# ENR_153_Board.net
KiCad netlist of a schematic drawn in EAGLE
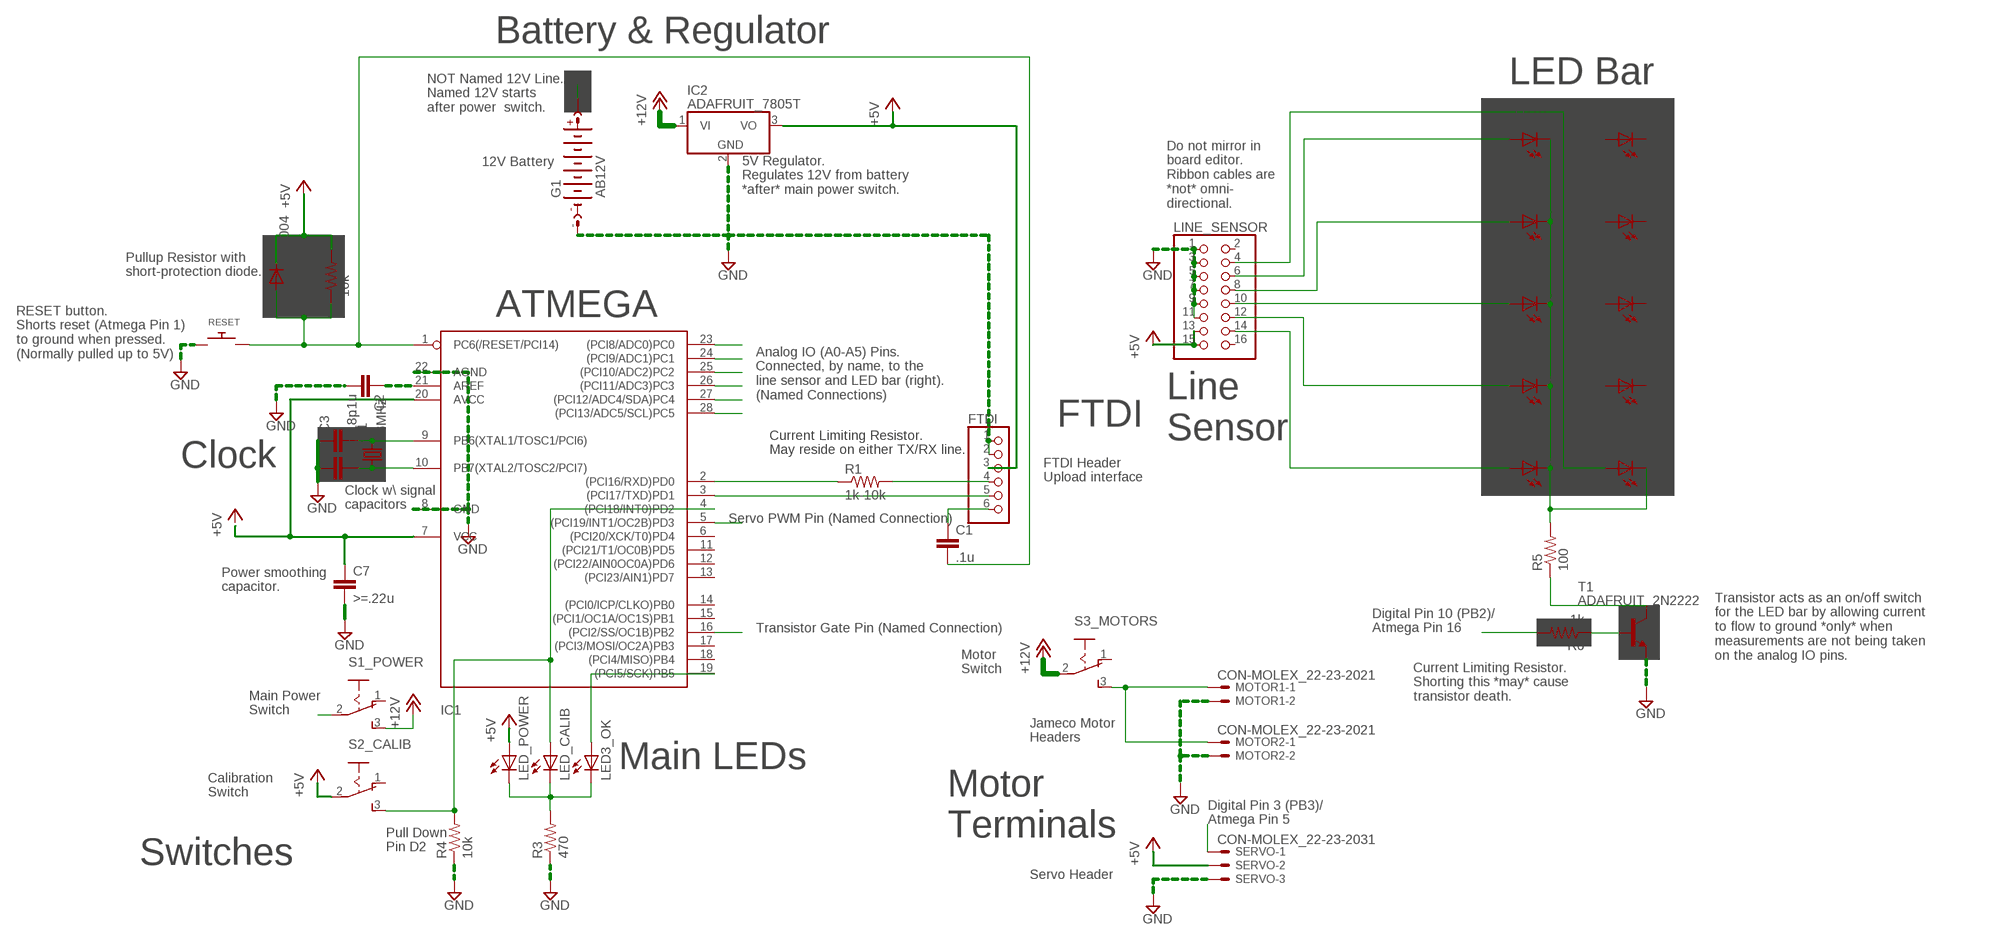
[diagram p0: schematic, sheet 1]

(export (version "E")
  (design (tool "Eeschema 10.0.6"))
  (components
    (comp (ref "C1")
      (value ".1u")
      (footprint "eagle-import:CAPACITOR-WIMA_C5B3")
      (libsource (lib "eagle-import") (part "CAPACITOR-WIMA_C5/3"))
    )
    (comp (ref "C2")
      (value ".1u")
      (footprint "eagle-import:CAPACITOR-WIMA_C5B3")
      (libsource (lib "eagle-import") (part "CAPACITOR-WIMA_C5/3"))
    )
    (comp (ref "C3")
      (value "18p")
      (footprint "eagle-import:CAPACITOR-WIMA_C5B3")
      (libsource (lib "eagle-import") (part "CAPACITOR-WIMA_C5/3"))
    )
    (comp (ref "C4")
      (value "18p")
      (footprint "eagle-import:CAPACITOR-WIMA_C5B3")
      (libsource (lib "eagle-import") (part "CAPACITOR-WIMA_C5/3"))
    )
    (comp (ref "C7")
      (value ">=.22u")
      (footprint "eagle-import:CAPACITOR-WIMA_C5B3")
      (libsource (lib "eagle-import") (part "CAPACITOR-WIMA_C5/3"))
    )
    (comp (ref "D1")
      (value "1N4004")
      (footprint "eagle-import:DIODE_DO35-7")
      (libsource (lib "eagle-import") (part "DIODE_1N4148DO35-7"))
    )
    (comp (ref "DZ1")
      (value "LB10")
      (footprint "eagle-import:LB10")
      (libsource (lib "eagle-import") (part "LB10"))
    )
    (comp (ref "FTDI")
      (value "PINHD-1X6")
      (footprint "eagle-import:1X06")
      (libsource (lib "eagle-import") (part "PINHD-1X6"))
    )
    (comp (ref "G1")
      (value "AB12V")
      (footprint "eagle-import:BATTERY_AB9V")
      (libsource (lib "eagle-import") (part "BATTERY_AB9V"))
    )
    (comp (ref "IC1")
      (value "ATMEGA168V-10P")
      (footprint "eagle-import:DIL28-3")
      (libsource (lib "eagle-import") (part "ATMEGA168PV-10"))
    )
    (comp (ref "IC2")
      (value "ADAFRUIT_7805T")
      (footprint "eagle-import:ADAFRUIT_TO220H")
      (libsource (lib "eagle-import") (part "ADAFRUIT_78T05"))
    )
    (comp (ref "LED3_OK")
      (value "ADAFRUIT_LEDSQR2X5")
      (footprint "eagle-import:ADAFRUIT_LED2X5")
      (libsource (lib "eagle-import") (part "ADAFRUIT_LEDSQR2X5"))
    )
    (comp (ref "LED_CALIB")
      (value "ADAFRUIT_LEDSQR2X5")
      (footprint "eagle-import:ADAFRUIT_LED2X5")
      (libsource (lib "eagle-import") (part "ADAFRUIT_LEDSQR2X5"))
    )
    (comp (ref "LED_POWER")
      (value "ADAFRUIT_LEDSQR2X5")
      (footprint "eagle-import:ADAFRUIT_LED2X5")
      (libsource (lib "eagle-import") (part "ADAFRUIT_LEDSQR2X5"))
    )
    (comp (ref "LINE_SENSOR")
      (value "PINHEAD_PINHD-2X8")
      (footprint "eagle-import:PINHEAD_2X08")
      (libsource (lib "eagle-import") (part "PINHEAD_PINHD-2X8"))
    )
    (comp (ref "MOTOR1")
      (value "CON-MOLEX_22-23-2021")
      (footprint "eagle-import:CON-MOLEX_22-23-2021")
      (fields (field (name "MF") "MOLEX") (field (name "MPN") "22-23-2021"))
      (libsource (lib "eagle-import") (part "CON-MOLEX_22-23-2021"))
    )
    (comp (ref "MOTOR2")
      (value "CON-MOLEX_22-23-2021")
      (footprint "eagle-import:CON-MOLEX_22-23-2021")
      (fields (field (name "MF") "MOLEX") (field (name "MPN") "22-23-2021"))
      (libsource (lib "eagle-import") (part "CON-MOLEX_22-23-2021"))
    )
    (comp (ref "Q1")
      (value "16MHz")
      (footprint "eagle-import:ADAFRUIT_HC49_S")
      (libsource (lib "eagle-import") (part "ADAFRUIT_CRYSTALHC49S"))
    )
    (comp (ref "R1")
      (value "1k-10k")
      (footprint "eagle-import:ADAFRUIT_0207_7")
      (libsource (lib "eagle-import") (part "ADAFRUIT_R-US_0207/7"))
    )
    (comp (ref "R2")
      (value "10k")
      (footprint "eagle-import:ADAFRUIT_0207_7")
      (libsource (lib "eagle-import") (part "ADAFRUIT_R-US_0207/7"))
    )
    (comp (ref "R3")
      (value "470")
      (footprint "eagle-import:ADAFRUIT_0207_7")
      (libsource (lib "eagle-import") (part "ADAFRUIT_R-US_0207/7"))
    )
    (comp (ref "R4")
      (value "10k")
      (footprint "eagle-import:ADAFRUIT_0207_7")
      (libsource (lib "eagle-import") (part "ADAFRUIT_R-US_0207/7"))
    )
    (comp (ref "R5")
      (value "100")
      (footprint "eagle-import:ADAFRUIT_0207_7")
      (libsource (lib "eagle-import") (part "ADAFRUIT_R-US_0207/7"))
    )
    (comp (ref "R6")
      (value "1k")
      (footprint "eagle-import:ADAFRUIT_0207_7")
      (libsource (lib "eagle-import") (part "ADAFRUIT_R-US_0207/7"))
    )
    (comp (ref "RESET")
      (value "ADAFRUIT_SWITCH_PUSHBUTTONEVQ-PE")
      (footprint "eagle-import:ADAFRUIT_TACT_PANA-EVQ")
      (libsource (lib "eagle-import") (part "ADAFRUIT_SWITCH_PUSHBUTTONEVQ-PE"))
    )
    (comp (ref "S1_POWER")
      (value "SWITCH_255SB")
      (footprint "eagle-import:SWITCH_255SB")
      (libsource (lib "eagle-import") (part "SWITCH_255SB"))
    )
    (comp (ref "S2_CALIB")
      (value "SWITCH_255SB")
      (footprint "eagle-import:SWITCH_255SB")
      (libsource (lib "eagle-import") (part "SWITCH_255SB"))
    )
    (comp (ref "S3_MOTORS")
      (value "SWITCH_255SB")
      (footprint "eagle-import:SWITCH_255SB")
      (libsource (lib "eagle-import") (part "SWITCH_255SB"))
    )
    (comp (ref "SERVO")
      (value "CON-MOLEX_22-23-2031")
      (footprint "eagle-import:CON-MOLEX_22-23-2031")
      (fields (field (name "MF") "MOLEX") (field (name "MPN") "22-23-2031"))
      (libsource (lib "eagle-import") (part "CON-MOLEX_22-23-2031"))
    )
    (comp (ref "T1")
      (value "ADAFRUIT_2N2222")
      (footprint "eagle-import:ADAFRUIT_TO92-EBC-OVAL")
      (libsource (lib "eagle-import") (part "ADAFRUIT_2N2222"))
    )
  )
  (nets
    (net (code "1") (name "+5V") (class "Default")
      (node (ref "C7") (pin "1") (pinfunction "1_1") (pintype "passive"))
      (node (ref "D1") (pin "C") (pinfunction "C_C") (pintype "passive"))
      (node (ref "FTDI") (pin "3") (pinfunction "3_3") (pintype "passive"))
      (node (ref "IC1") (pin "20") (pinfunction "AVCC_20") (pintype "bidirectional"))
      (node (ref "IC1") (pin "7") (pinfunction "VCC_7") (pintype "bidirectional"))
      (node (ref "IC2") (pin "3") (pinfunction "VO_3") (pintype "passive"))
      (node (ref "LED_POWER") (pin "A") (pinfunction "A_A") (pintype "passive"))
      (node (ref "LINE_SENSOR") (pin "13") (pinfunction "13_13") (pintype "passive"))
      (node (ref "LINE_SENSOR") (pin "15") (pinfunction "15_15") (pintype "passive"))
      (node (ref "R2") (pin "2") (pinfunction "2_2") (pintype "passive"))
      (node (ref "S2_CALIB") (pin "2") (pinfunction "P_2") (pintype "passive"))
      (node (ref "SERVO") (pin "2") (pinfunction "S_2") (pintype "passive"))
    )
    (net (code "2") (name "+12V") (class "Default")
      (node (ref "IC2") (pin "1") (pinfunction "VI_1") (pintype "input"))
      (node (ref "S1_POWER") (pin "3") (pinfunction "S_3") (pintype "passive"))
      (node (ref "S3_MOTORS") (pin "2") (pinfunction "P_2") (pintype "passive"))
    )
    (net (code "3") (name "/A0") (class "Default")
      (node (ref "DZ1") (pin "6") (pinfunction "A_6") (pintype "passive"))
      (node (ref "IC1") (pin "23") (pinfunction "(PCI8/ADC0)PC0_23") (pintype "bidirectional"))
      (node (ref "LINE_SENSOR") (pin "4") (pinfunction "4_4") (pintype "passive"))
    )
    (net (code "4") (name "/A1") (class "Default")
      (node (ref "DZ1") (pin "5") (pinfunction "A_5") (pintype "passive"))
      (node (ref "IC1") (pin "24") (pinfunction "(PCI9/ADC1)PC1_24") (pintype "bidirectional"))
      (node (ref "LINE_SENSOR") (pin "6") (pinfunction "6_6") (pintype "passive"))
    )
    (net (code "5") (name "/A2") (class "Default")
      (node (ref "DZ1") (pin "4") (pinfunction "A_4") (pintype "passive"))
      (node (ref "IC1") (pin "25") (pinfunction "(PCI10/ADC2)PC2_25") (pintype "bidirectional"))
      (node (ref "LINE_SENSOR") (pin "8") (pinfunction "8_8") (pintype "passive"))
    )
    (net (code "6") (name "/A3") (class "Default")
      (node (ref "DZ1") (pin "3") (pinfunction "A_3") (pintype "passive"))
      (node (ref "IC1") (pin "26") (pinfunction "(PCI11/ADC3)PC3_26") (pintype "bidirectional"))
      (node (ref "LINE_SENSOR") (pin "10") (pinfunction "10_10") (pintype "passive"))
    )
    (net (code "7") (name "/A4") (class "Default")
      (node (ref "DZ1") (pin "2") (pinfunction "A_2") (pintype "passive"))
      (node (ref "IC1") (pin "27") (pinfunction "(PCI12/ADC4/SDA)PC4_27") (pintype "bidirectional"))
      (node (ref "LINE_SENSOR") (pin "12") (pinfunction "12_12") (pintype "passive"))
    )
    (net (code "8") (name "/A5") (class "Default")
      (node (ref "DZ1") (pin "1") (pinfunction "A_1") (pintype "passive"))
      (node (ref "IC1") (pin "28") (pinfunction "(PCI13/ADC5/SCL)PC5_28") (pintype "bidirectional"))
      (node (ref "LINE_SENSOR") (pin "14") (pinfunction "14_14") (pintype "passive"))
    )
    (net (code "9") (name "/MAINS") (class "Default")
      (node (ref "G1") (pin "+") (pinfunction "+_+") (pintype "passive"))
      (node (ref "S1_POWER") (pin "2") (pinfunction "P_2") (pintype "passive"))
    )
    (net (code "10") (name "/SERVO") (class "Default")
      (node (ref "IC1") (pin "5") (pinfunction "(PCI19/INT1/OC2B)PD3_5") (pintype "bidirectional"))
      (node (ref "SERVO") (pin "1") (pinfunction "S_1") (pintype "passive"))
    )
    (net (code "11") (name "/TRANSISTOR_GATE") (class "Default")
      (node (ref "IC1") (pin "16") (pinfunction "(PCI2/SS/OC1B)PB2_16") (pintype "bidirectional"))
      (node (ref "R6") (pin "2") (pinfunction "2_2") (pintype "passive"))
    )
    (net (code "12") (name "GND") (class "Default")
      (node (ref "C2") (pin "2") (pinfunction "2_2") (pintype "passive"))
      (node (ref "C3") (pin "1") (pinfunction "1_1") (pintype "passive"))
      (node (ref "C4") (pin "1") (pinfunction "1_1") (pintype "passive"))
      (node (ref "C7") (pin "2") (pinfunction "2_2") (pintype "passive"))
      (node (ref "FTDI") (pin "1") (pinfunction "1_1") (pintype "passive"))
      (node (ref "FTDI") (pin "2") (pinfunction "2_2") (pintype "passive"))
      (node (ref "G1") (pin "-") (pinfunction "-_-") (pintype "passive"))
      (node (ref "IC1") (pin "22") (pinfunction "AGND_22") (pintype "bidirectional"))
      (node (ref "IC1") (pin "8") (pinfunction "GND_8") (pintype "bidirectional"))
      (node (ref "IC2") (pin "2") (pinfunction "GND_2") (pintype "passive"))
      (node (ref "LINE_SENSOR") (pin "1") (pinfunction "1_1") (pintype "passive"))
      (node (ref "LINE_SENSOR") (pin "11") (pinfunction "11_11") (pintype "passive"))
      (node (ref "LINE_SENSOR") (pin "3") (pinfunction "3_3") (pintype "passive"))
      (node (ref "LINE_SENSOR") (pin "5") (pinfunction "5_5") (pintype "passive"))
      (node (ref "LINE_SENSOR") (pin "7") (pinfunction "7_7") (pintype "passive"))
      (node (ref "LINE_SENSOR") (pin "9") (pinfunction "9_9") (pintype "passive"))
      (node (ref "MOTOR1") (pin "2") (pinfunction "S_2") (pintype "passive"))
      (node (ref "MOTOR2") (pin "2") (pinfunction "S_2") (pintype "passive"))
      (node (ref "R3") (pin "1") (pinfunction "1_1") (pintype "passive"))
      (node (ref "R4") (pin "1") (pinfunction "1_1") (pintype "passive"))
      (node (ref "RESET") (pin "P$1") (pinfunction "P$1_P$1") (pintype "passive"))
      (node (ref "SERVO") (pin "3") (pinfunction "S_3") (pintype "passive"))
      (node (ref "T1") (pin "E") (pinfunction "E_E") (pintype "passive"))
    )
    (net (code "13") (name "Net-(C1-Pad1)") (class "Default")
      (node (ref "C1") (pin "1") (pinfunction "1_1") (pintype "passive"))
      (node (ref "FTDI") (pin "6") (pinfunction "6_6") (pintype "passive"))
    )
    (net (code "14") (name "Net-(DZ1A-C)") (class "Default")
      (node (ref "DZ1") (pin "15") (pinfunction "C_15") (pintype "passive"))
      (node (ref "DZ1") (pin "16") (pinfunction "C_16") (pintype "passive"))
      (node (ref "DZ1") (pin "17") (pinfunction "C_17") (pintype "passive"))
      (node (ref "DZ1") (pin "18") (pinfunction "C_18") (pintype "passive"))
      (node (ref "DZ1") (pin "19") (pinfunction "C_19") (pintype "passive"))
      (node (ref "DZ1") (pin "20") (pinfunction "C_20") (pintype "passive"))
      (node (ref "R5") (pin "2") (pinfunction "2_2") (pintype "passive"))
    )
    (net (code "15") (name "Net-(FTDI-Pad4)") (class "Default")
      (node (ref "FTDI") (pin "4") (pinfunction "4_4") (pintype "passive"))
      (node (ref "R1") (pin "2") (pinfunction "2_2") (pintype "passive"))
    )
    (net (code "16") (name "Net-(IC1-(PCI5{slash}SCK)PB5)") (class "Default")
      (node (ref "IC1") (pin "19") (pinfunction "(PCI5/SCK)PB5_19") (pintype "bidirectional"))
      (node (ref "LED3_OK") (pin "A") (pinfunction "A_A") (pintype "passive"))
    )
    (net (code "17") (name "Net-(IC1-(PCI16{slash}RXD)PD0)") (class "Default")
      (node (ref "IC1") (pin "2") (pinfunction "(PCI16/RXD)PD0_2") (pintype "bidirectional"))
      (node (ref "R1") (pin "1") (pinfunction "1_1") (pintype "passive"))
    )
    (net (code "18") (name "Net-(IC1-(PCI17{slash}TXD)PD1)") (class "Default")
      (node (ref "FTDI") (pin "5") (pinfunction "5_5") (pintype "passive"))
      (node (ref "IC1") (pin "3") (pinfunction "(PCI17/TXD)PD1_3") (pintype "bidirectional"))
    )
    (net (code "19") (name "Net-(IC1-(PCI18{slash}INT0)PD2)") (class "Default")
      (node (ref "IC1") (pin "4") (pinfunction "(PCI18/INT0)PD2_4") (pintype "bidirectional"))
      (node (ref "LED_CALIB") (pin "A") (pinfunction "A_A") (pintype "passive"))
      (node (ref "R4") (pin "2") (pinfunction "2_2") (pintype "passive"))
      (node (ref "S2_CALIB") (pin "3") (pinfunction "S_3") (pintype "passive"))
    )
    (net (code "20") (name "Net-(IC1-AREF)") (class "Default")
      (node (ref "C2") (pin "1") (pinfunction "1_1") (pintype "passive"))
      (node (ref "IC1") (pin "21") (pinfunction "AREF_21") (pintype "bidirectional"))
    )
    (net (code "21") (name "Net-(IC1-PB6(XTAL1{slash}TOSC1{slash}PCI6))") (class "Default")
      (node (ref "C3") (pin "2") (pinfunction "2_2") (pintype "passive"))
      (node (ref "IC1") (pin "9") (pinfunction "PB6(XTAL1/TOSC1/PCI6)_9") (pintype "bidirectional"))
      (node (ref "Q1") (pin "2") (pinfunction "2_2") (pintype "passive"))
    )
    (net (code "22") (name "Net-(IC1-PB7(XTAL2{slash}TOSC2{slash}PCI7))") (class "Default")
      (node (ref "C4") (pin "2") (pinfunction "2_2") (pintype "passive"))
      (node (ref "IC1") (pin "10") (pinfunction "PB7(XTAL2/TOSC2/PCI7)_10") (pintype "bidirectional"))
      (node (ref "Q1") (pin "1") (pinfunction "1_1") (pintype "passive"))
    )
    (net (code "23") (name "Net-(IC1-PC6({slash}RESET{slash}PCI14))") (class "Default")
      (node (ref "C1") (pin "2") (pinfunction "2_2") (pintype "passive"))
      (node (ref "D1") (pin "A") (pinfunction "A_A") (pintype "passive"))
      (node (ref "IC1") (pin "1") (pinfunction "PC6(/RESET/PCI14)_1") (pintype "bidirectional"))
      (node (ref "R2") (pin "1") (pinfunction "1_1") (pintype "passive"))
      (node (ref "RESET") (pin "P$2") (pinfunction "P$2_P$2") (pintype "passive"))
    )
    (net (code "24") (name "Net-(LED3_OK-C)") (class "Default")
      (node (ref "LED3_OK") (pin "K") (pinfunction "C_K") (pintype "passive"))
      (node (ref "LED_CALIB") (pin "K") (pinfunction "C_K") (pintype "passive"))
      (node (ref "LED_POWER") (pin "K") (pinfunction "C_K") (pintype "passive"))
      (node (ref "R3") (pin "2") (pinfunction "2_2") (pintype "passive"))
    )
    (net (code "25") (name "Net-(MOTOR1A-S)") (class "Default")
      (node (ref "MOTOR1") (pin "1") (pinfunction "S_1") (pintype "passive"))
      (node (ref "MOTOR2") (pin "1") (pinfunction "S_1") (pintype "passive"))
      (node (ref "S3_MOTORS") (pin "3") (pinfunction "S_3") (pintype "passive"))
    )
    (net (code "26") (name "Net-(R5-Pad1)") (class "Default")
      (node (ref "R5") (pin "1") (pinfunction "1_1") (pintype "passive"))
      (node (ref "T1") (pin "C") (pinfunction "C_C") (pintype "passive"))
    )
    (net (code "27") (name "Net-(R6-Pad1)") (class "Default")
      (node (ref "R6") (pin "1") (pinfunction "1_1") (pintype "passive"))
      (node (ref "T1") (pin "B") (pinfunction "B_B") (pintype "passive"))
    )
    (net (code "28") (name "unconnected-(DZ1B-A-Pad10)") (class "Default")
      (node (ref "DZ1") (pin "10") (pinfunction "A_10") (pintype "passive"))
    )
    (net (code "29") (name "unconnected-(DZ1B-C-Pad11)") (class "Default")
      (node (ref "DZ1") (pin "11") (pinfunction "C_11") (pintype "passive"))
    )
    (net (code "30") (name "unconnected-(DZ1H-A-Pad7)") (class "Default")
      (node (ref "DZ1") (pin "7") (pinfunction "A_7") (pintype "passive"))
    )
    (net (code "31") (name "unconnected-(DZ1H-C-Pad14)") (class "Default")
      (node (ref "DZ1") (pin "14") (pinfunction "C_14") (pintype "passive"))
    )
    (net (code "32") (name "unconnected-(DZ1I-A-Pad8)") (class "Default")
      (node (ref "DZ1") (pin "8") (pinfunction "A_8") (pintype "passive"))
    )
    (net (code "33") (name "unconnected-(DZ1I-C-Pad13)") (class "Default")
      (node (ref "DZ1") (pin "13") (pinfunction "C_13") (pintype "passive"))
    )
    (net (code "34") (name "unconnected-(DZ1J-A-Pad9)") (class "Default")
      (node (ref "DZ1") (pin "9") (pinfunction "A_9") (pintype "passive"))
    )
    (net (code "35") (name "unconnected-(DZ1J-C-Pad12)") (class "Default")
      (node (ref "DZ1") (pin "12") (pinfunction "C_12") (pintype "passive"))
    )
    (net (code "36") (name "unconnected-(IC1-(PCI0{slash}ICP{slash}CLKO)PB0-Pad14)") (class "Default")
      (node (ref "IC1") (pin "14") (pinfunction "(PCI0/ICP/CLKO)PB0_14") (pintype "bidirectional"))
    )
    (net (code "37") (name "unconnected-(IC1-(PCI1{slash}OC1A{slash}OC1S)PB1-Pad15)") (class "Default")
      (node (ref "IC1") (pin "15") (pinfunction "(PCI1/OC1A/OC1S)PB1_15") (pintype "bidirectional"))
    )
    (net (code "38") (name "unconnected-(IC1-(PCI3{slash}MOSI{slash}OC2A)PB3-Pad17)") (class "Default")
      (node (ref "IC1") (pin "17") (pinfunction "(PCI3/MOSI/OC2A)PB3_17") (pintype "bidirectional"))
    )
    (net (code "39") (name "unconnected-(IC1-(PCI4{slash}MISO)PB4-Pad18)") (class "Default")
      (node (ref "IC1") (pin "18") (pinfunction "(PCI4/MISO)PB4_18") (pintype "bidirectional"))
    )
    (net (code "40") (name "unconnected-(IC1-(PCI20{slash}XCK{slash}T0)PD4-Pad6)") (class "Default")
      (node (ref "IC1") (pin "6") (pinfunction "(PCI20/XCK/T0)PD4_6") (pintype "bidirectional"))
    )
    (net (code "41") (name "unconnected-(IC1-(PCI21{slash}T1{slash}OC0B)PD5-Pad11)") (class "Default")
      (node (ref "IC1") (pin "11") (pinfunction "(PCI21/T1/OC0B)PD5_11") (pintype "bidirectional"))
    )
    (net (code "42") (name "unconnected-(IC1-(PCI22{slash}AIN0OC0A)PD6-Pad12)") (class "Default")
      (node (ref "IC1") (pin "12") (pinfunction "(PCI22/AIN0OC0A)PD6_12") (pintype "bidirectional"))
    )
    (net (code "43") (name "unconnected-(IC1-(PCI23{slash}AIN1)PD7-Pad13)") (class "Default")
      (node (ref "IC1") (pin "13") (pinfunction "(PCI23/AIN1)PD7_13") (pintype "bidirectional"))
    )
    (net (code "44") (name "unconnected-(LINE_SENSOR-Pad2)") (class "Default")
      (node (ref "LINE_SENSOR") (pin "2") (pinfunction "2_2") (pintype "passive"))
    )
    (net (code "45") (name "unconnected-(LINE_SENSOR-Pad16)") (class "Default")
      (node (ref "LINE_SENSOR") (pin "16") (pinfunction "16_16") (pintype "passive"))
    )
    (net (code "46") (name "unconnected-(S1_POWER-O-Pad1)") (class "Default")
      (node (ref "S1_POWER") (pin "1") (pinfunction "O_1") (pintype "passive"))
    )
    (net (code "47") (name "unconnected-(S2_CALIB-O-Pad1)") (class "Default")
      (node (ref "S2_CALIB") (pin "1") (pinfunction "O_1") (pintype "passive"))
    )
    (net (code "48") (name "unconnected-(S3_MOTORS-O-Pad1)") (class "Default")
      (node (ref "S3_MOTORS") (pin "1") (pinfunction "O_1") (pintype "passive"))
    )
  )
)
